# Shema_v4.net
KiCad netlist of a schematic drawn in Altium Designer
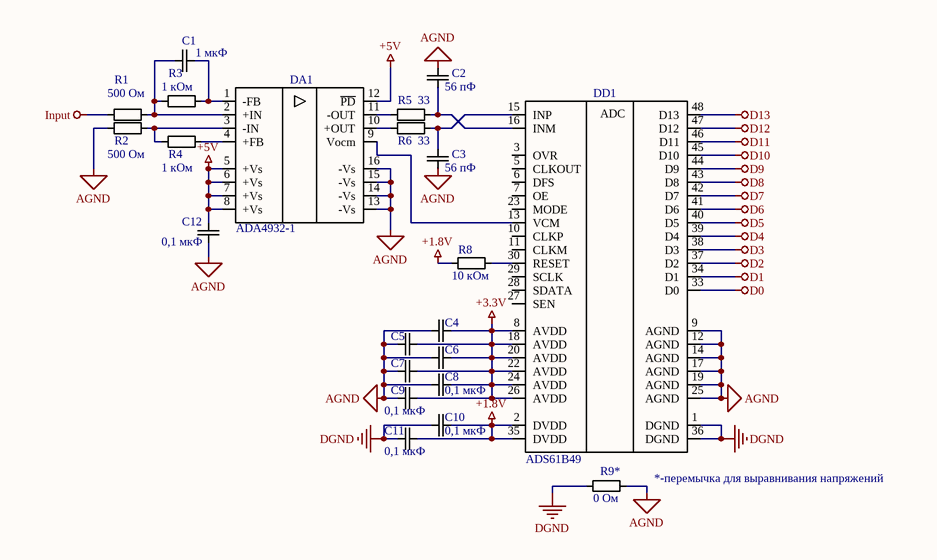
[diagram p0: Shema_v4.SchDoc]

(export (version "E")
  (design (tool "Eeschema 10.0.6"))
  (components
    (comp (ref "C1")
      (value "1 мкФ")
      (footprint "RC0603")
      (description "Конденсатор")
      (libsource (lib "V_4") (part "Capacitor"))
    )
    (comp (ref "C2")
      (value "56 пФ")
      (footprint "RC0603")
      (description "Конденсатор")
      (libsource (lib "V_4") (part "Capacitor"))
    )
    (comp (ref "C3")
      (value "56 пФ")
      (footprint "RC0603")
      (description "Конденсатор")
      (libsource (lib "V_4") (part "Capacitor"))
    )
    (comp (ref "C4")
      (value "0,1 мкФ")
      (footprint "RC0402")
      (description "Конденсатор")
      (libsource (lib "V_4") (part "Capacitor"))
    )
    (comp (ref "C5")
      (value "0,1 мкФ")
      (footprint "RC0402")
      (description "Конденсатор")
      (libsource (lib "V_4") (part "Capacitor"))
    )
    (comp (ref "C6")
      (value "0,1 мкФ")
      (footprint "RC0402")
      (description "Конденсатор")
      (libsource (lib "V_4") (part "Capacitor"))
    )
    (comp (ref "C7")
      (value "0,1 мкФ")
      (footprint "RC0402")
      (description "Конденсатор")
      (libsource (lib "V_4") (part "Capacitor"))
    )
    (comp (ref "C8")
      (value "0,1 мкФ")
      (footprint "RC0402")
      (description "Конденсатор")
      (libsource (lib "V_4") (part "Capacitor"))
    )
    (comp (ref "C9")
      (value "0,1 мкФ")
      (footprint "RC0402")
      (description "Конденсатор")
      (libsource (lib "V_4") (part "Capacitor"))
    )
    (comp (ref "C10")
      (value "0,1 мкФ")
      (footprint "RC0402")
      (description "Конденсатор")
      (libsource (lib "V_4") (part "Capacitor"))
    )
    (comp (ref "C11")
      (value "0,1 мкФ")
      (footprint "RC0402")
      (description "Конденсатор")
      (libsource (lib "V_4") (part "Capacitor"))
    )
    (comp (ref "C12")
      (value "0,1 мкФ")
      (footprint "RC0402")
      (description "Конденсатор")
      (libsource (lib "V_4") (part "Capacitor"))
    )
    (comp (ref "DA1")
      (value "ADA4932-1")
      (footprint "QFN16")
      (description "Операционный усилитель для АЦП")
      (libsource (lib "V_4") (part "ADA4932-1"))
    )
    (comp (ref "DD1")
      (value "ADS61B49")
      (footprint "QFN48")
      (description "14-бит АЦП")
      (libsource (lib "V_4") (part "ADS61B49"))
    )
    (comp (ref "R1")
      (value "500 Ом")
      (footprint "RC0603")
      (description "Резистор")
      (libsource (lib "") (part "Resistor_1"))
    )
    (comp (ref "R2")
      (value "500 Ом")
      (footprint "RC0603")
      (description "Резистор")
      (libsource (lib "V_4") (part "Resistor"))
    )
    (comp (ref "R3")
      (value "1 кОм")
      (footprint "RC0603")
      (description "Резистор")
      (libsource (lib "") (part "Resistor_1"))
    )
    (comp (ref "R4")
      (value "1 кОм")
      (footprint "RC0603")
      (description "Резистор")
      (libsource (lib "") (part "Resistor_1"))
    )
    (comp (ref "R5")
      (value "33")
      (footprint "RC0603")
      (description "Резистор")
      (libsource (lib "") (part "Resistor_1"))
    )
    (comp (ref "R6")
      (value "33")
      (footprint "RC0603")
      (description "Резистор")
      (libsource (lib "") (part "Resistor_1"))
    )
    (comp (ref "R8")
      (value "10 кОм")
      (footprint "RC0603")
      (description "Резистор")
      (libsource (lib "V_4") (part "Resistor"))
    )
    (comp (ref "R9*")
      (value "0 Ом")
      (footprint "RC0402")
      (description "Резистор")
      (libsource (lib "V_4") (part "Resistor"))
    )
  )
  (nets
    (net (code "1") (name "+1.8V") (class "Default")
      (node (ref "C10") (pin "1") (pinfunction "1_1") (pintype "passive"))
      (node (ref "C11") (pin "1") (pinfunction "1_1") (pintype "passive"))
      (node (ref "DD1") (pin "2") (pinfunction "DVDD_2") (pintype "passive"))
      (node (ref "DD1") (pin "35") (pinfunction "DVDD_35") (pintype "passive"))
      (node (ref "R8") (pin "2") (pinfunction "2_2") (pintype "passive"))
    )
    (net (code "2") (name "+3.3V") (class "Default")
      (node (ref "C4") (pin "1") (pinfunction "1_1") (pintype "passive"))
      (node (ref "C5") (pin "1") (pinfunction "1_1") (pintype "passive"))
      (node (ref "C6") (pin "1") (pinfunction "1_1") (pintype "passive"))
      (node (ref "C7") (pin "1") (pinfunction "1_1") (pintype "passive"))
      (node (ref "C8") (pin "1") (pinfunction "1_1") (pintype "passive"))
      (node (ref "C9") (pin "1") (pinfunction "1_1") (pintype "passive"))
      (node (ref "DD1") (pin "18") (pinfunction "AVDD_18") (pintype "passive"))
      (node (ref "DD1") (pin "20") (pinfunction "AVDD_20") (pintype "passive"))
      (node (ref "DD1") (pin "22") (pinfunction "AVDD_22") (pintype "passive"))
      (node (ref "DD1") (pin "24") (pinfunction "AVDD_24") (pintype "passive"))
      (node (ref "DD1") (pin "26") (pinfunction "AVDD_26") (pintype "passive"))
      (node (ref "DD1") (pin "8") (pinfunction "AVDD_8") (pintype "passive"))
    )
    (net (code "3") (name "+5V") (class "Default")
      (node (ref "C12") (pin "1") (pinfunction "1_1") (pintype "passive"))
      (node (ref "DA1") (pin "12") (pinfunction "PD_12") (pintype "passive"))
      (node (ref "DA1") (pin "5") (pinfunction "+Vs_5") (pintype "passive"))
      (node (ref "DA1") (pin "6") (pinfunction "+Vs_6") (pintype "passive"))
      (node (ref "DA1") (pin "7") (pinfunction "+Vs_7") (pintype "passive"))
      (node (ref "DA1") (pin "8") (pinfunction "+Vs_8") (pintype "passive"))
    )
    (net (code "4") (name "AGND") (class "Default")
      (node (ref "C12") (pin "2") (pinfunction "2_2") (pintype "passive"))
      (node (ref "C2") (pin "2") (pinfunction "2_2") (pintype "passive"))
      (node (ref "C3") (pin "1") (pinfunction "1_1") (pintype "passive"))
      (node (ref "C4") (pin "2") (pinfunction "2_2") (pintype "passive"))
      (node (ref "C5") (pin "2") (pinfunction "2_2") (pintype "passive"))
      (node (ref "C6") (pin "2") (pinfunction "2_2") (pintype "passive"))
      (node (ref "C7") (pin "2") (pinfunction "2_2") (pintype "passive"))
      (node (ref "C8") (pin "2") (pinfunction "2_2") (pintype "passive"))
      (node (ref "C9") (pin "2") (pinfunction "2_2") (pintype "passive"))
      (node (ref "DA1") (pin "13") (pinfunction "-Vs_13") (pintype "passive"))
      (node (ref "DA1") (pin "14") (pinfunction "-Vs_14") (pintype "passive"))
      (node (ref "DA1") (pin "15") (pinfunction "-Vs_15") (pintype "passive"))
      (node (ref "DA1") (pin "16") (pinfunction "-Vs_16") (pintype "passive"))
      (node (ref "DD1") (pin "12") (pinfunction "AGND_12") (pintype "passive"))
      (node (ref "DD1") (pin "14") (pinfunction "AGND_14") (pintype "passive"))
      (node (ref "DD1") (pin "17") (pinfunction "AGND_17") (pintype "passive"))
      (node (ref "DD1") (pin "19") (pinfunction "AGND_19") (pintype "passive"))
      (node (ref "DD1") (pin "25") (pinfunction "AGND_25") (pintype "passive"))
      (node (ref "DD1") (pin "9") (pinfunction "AGND_9") (pintype "passive"))
      (node (ref "R2") (pin "2") (pinfunction "2_2") (pintype "passive"))
      (node (ref "R9*") (pin "1") (pinfunction "1_1") (pintype "passive"))
    )
    (net (code "5") (name "D0") (class "Default")
      (node (ref "DD1") (pin "33") (pinfunction "D0_33") (pintype "passive"))
    )
    (net (code "6") (name "D1") (class "Default")
      (node (ref "DD1") (pin "34") (pinfunction "D1_34") (pintype "passive"))
    )
    (net (code "7") (name "D2") (class "Default")
      (node (ref "DD1") (pin "37") (pinfunction "D2_37") (pintype "passive"))
    )
    (net (code "8") (name "D3") (class "Default")
      (node (ref "DD1") (pin "38") (pinfunction "D3_38") (pintype "passive"))
    )
    (net (code "9") (name "D4") (class "Default")
      (node (ref "DD1") (pin "39") (pinfunction "D4_39") (pintype "passive"))
    )
    (net (code "10") (name "D5") (class "Default")
      (node (ref "DD1") (pin "40") (pinfunction "D5_40") (pintype "passive"))
    )
    (net (code "11") (name "D6") (class "Default")
      (node (ref "DD1") (pin "41") (pinfunction "D6_41") (pintype "passive"))
    )
    (net (code "12") (name "D7") (class "Default")
      (node (ref "DD1") (pin "42") (pinfunction "D7_42") (pintype "passive"))
    )
    (net (code "13") (name "D8") (class "Default")
      (node (ref "DD1") (pin "43") (pinfunction "D8_43") (pintype "passive"))
    )
    (net (code "14") (name "D9") (class "Default")
      (node (ref "DD1") (pin "44") (pinfunction "D9_44") (pintype "passive"))
    )
    (net (code "15") (name "D10") (class "Default")
      (node (ref "DD1") (pin "45") (pinfunction "D10_45") (pintype "passive"))
    )
    (net (code "16") (name "D11") (class "Default")
      (node (ref "DD1") (pin "46") (pinfunction "D11_46") (pintype "passive"))
    )
    (net (code "17") (name "D12") (class "Default")
      (node (ref "DD1") (pin "47") (pinfunction "D12_47") (pintype "passive"))
    )
    (net (code "18") (name "D13") (class "Default")
      (node (ref "DD1") (pin "48") (pinfunction "D13_48") (pintype "passive"))
    )
    (net (code "19") (name "DGND") (class "Default")
      (node (ref "C10") (pin "2") (pinfunction "2_2") (pintype "passive"))
      (node (ref "C11") (pin "2") (pinfunction "2_2") (pintype "passive"))
      (node (ref "DD1") (pin "1") (pinfunction "DGND_1") (pintype "passive"))
      (node (ref "DD1") (pin "36") (pinfunction "DGND_36") (pintype "passive"))
      (node (ref "R9*") (pin "2") (pinfunction "2_2") (pintype "passive"))
    )
    (net (code "20") (name "Input") (class "Default")
      (node (ref "R1") (pin "1") (pinfunction "1_1") (pintype "passive"))
    )
    (net (code "21") (name "Net-(DA1-+FB)") (class "Default")
      (node (ref "DA1") (pin "4") (pinfunction "+FB_4") (pintype "passive"))
      (node (ref "R4") (pin "2") (pinfunction "2_2") (pintype "passive"))
    )
    (net (code "22") (name "Net-(DA1-+IN)") (class "Default")
      (node (ref "C1") (pin "1") (pinfunction "1_1") (pintype "passive"))
      (node (ref "DA1") (pin "2") (pinfunction "+IN_2") (pintype "passive"))
      (node (ref "R1") (pin "2") (pinfunction "2_2") (pintype "passive"))
      (node (ref "R3") (pin "1") (pinfunction "1_1") (pintype "passive"))
    )
    (net (code "23") (name "Net-(DA1-+OUT)") (class "Default")
      (node (ref "DA1") (pin "10") (pinfunction "+OUT_10") (pintype "passive"))
      (node (ref "R6") (pin "1") (pinfunction "1_1") (pintype "passive"))
    )
    (net (code "24") (name "Net-(DA1--FB)") (class "Default")
      (node (ref "C1") (pin "2") (pinfunction "2_2") (pintype "passive"))
      (node (ref "DA1") (pin "1") (pinfunction "-FB_1") (pintype "passive"))
      (node (ref "R3") (pin "2") (pinfunction "2_2") (pintype "passive"))
    )
    (net (code "25") (name "Net-(DA1--IN)") (class "Default")
      (node (ref "DA1") (pin "3") (pinfunction "-IN_3") (pintype "passive"))
      (node (ref "R2") (pin "1") (pinfunction "1_1") (pintype "passive"))
      (node (ref "R4") (pin "1") (pinfunction "1_1") (pintype "passive"))
    )
    (net (code "26") (name "Net-(DA1--OUT)") (class "Default")
      (node (ref "DA1") (pin "11") (pinfunction "-OUT_11") (pintype "passive"))
      (node (ref "R5") (pin "1") (pinfunction "1_1") (pintype "passive"))
    )
    (net (code "27") (name "Net-(DA1-Vocm)") (class "Default")
      (node (ref "DA1") (pin "9") (pinfunction "Vocm_9") (pintype "passive"))
      (node (ref "DD1") (pin "13") (pinfunction "VCM_13") (pintype "passive"))
    )
    (net (code "28") (name "Net-(DD1-INM)") (class "Default")
      (node (ref "C2") (pin "1") (pinfunction "1_1") (pintype "passive"))
      (node (ref "DD1") (pin "16") (pinfunction "INM_16") (pintype "passive"))
      (node (ref "R5") (pin "2") (pinfunction "2_2") (pintype "passive"))
    )
    (net (code "29") (name "Net-(DD1-INP)") (class "Default")
      (node (ref "C3") (pin "2") (pinfunction "2_2") (pintype "passive"))
      (node (ref "DD1") (pin "15") (pinfunction "INP_15") (pintype "passive"))
      (node (ref "R6") (pin "2") (pinfunction "2_2") (pintype "passive"))
    )
    (net (code "30") (name "Net-(DD1-RESET)") (class "Default")
      (node (ref "DD1") (pin "30") (pinfunction "RESET_30") (pintype "passive"))
      (node (ref "R8") (pin "1") (pinfunction "1_1") (pintype "passive"))
    )
    (net (code "31") (name "unconnected-(DD1-CLKM-Pad11)") (class "Default")
      (node (ref "DD1") (pin "11") (pinfunction "CLKM_11") (pintype "passive"))
    )
    (net (code "32") (name "unconnected-(DD1-CLKOUT-Pad5)") (class "Default")
      (node (ref "DD1") (pin "5") (pinfunction "CLKOUT_5") (pintype "passive"))
    )
    (net (code "33") (name "unconnected-(DD1-CLKP-Pad10)") (class "Default")
      (node (ref "DD1") (pin "10") (pinfunction "CLKP_10") (pintype "passive"))
    )
    (net (code "34") (name "unconnected-(DD1-DFS-Pad6)") (class "Default")
      (node (ref "DD1") (pin "6") (pinfunction "DFS_6") (pintype "passive"))
    )
    (net (code "35") (name "unconnected-(DD1-MODE-Pad23)") (class "Default")
      (node (ref "DD1") (pin "23") (pinfunction "MODE_23") (pintype "passive"))
    )
    (net (code "36") (name "unconnected-(DD1-OE-Pad7)") (class "Default")
      (node (ref "DD1") (pin "7") (pinfunction "OE_7") (pintype "passive"))
    )
    (net (code "37") (name "unconnected-(DD1-OVR-Pad3)") (class "Default")
      (node (ref "DD1") (pin "3") (pinfunction "OVR_3") (pintype "passive"))
    )
    (net (code "38") (name "unconnected-(DD1-SCLK-Pad29)") (class "Default")
      (node (ref "DD1") (pin "29") (pinfunction "SCLK_29") (pintype "passive"))
    )
    (net (code "39") (name "unconnected-(DD1-SDATA-Pad28)") (class "Default")
      (node (ref "DD1") (pin "28") (pinfunction "SDATA_28") (pintype "passive"))
    )
    (net (code "40") (name "unconnected-(DD1-SEN-Pad27)") (class "Default")
      (node (ref "DD1") (pin "27") (pinfunction "SEN_27") (pintype "passive"))
    )
  )
)
